# prjct_1.net
KiCad netlist of a schematic drawn in EasyEDA
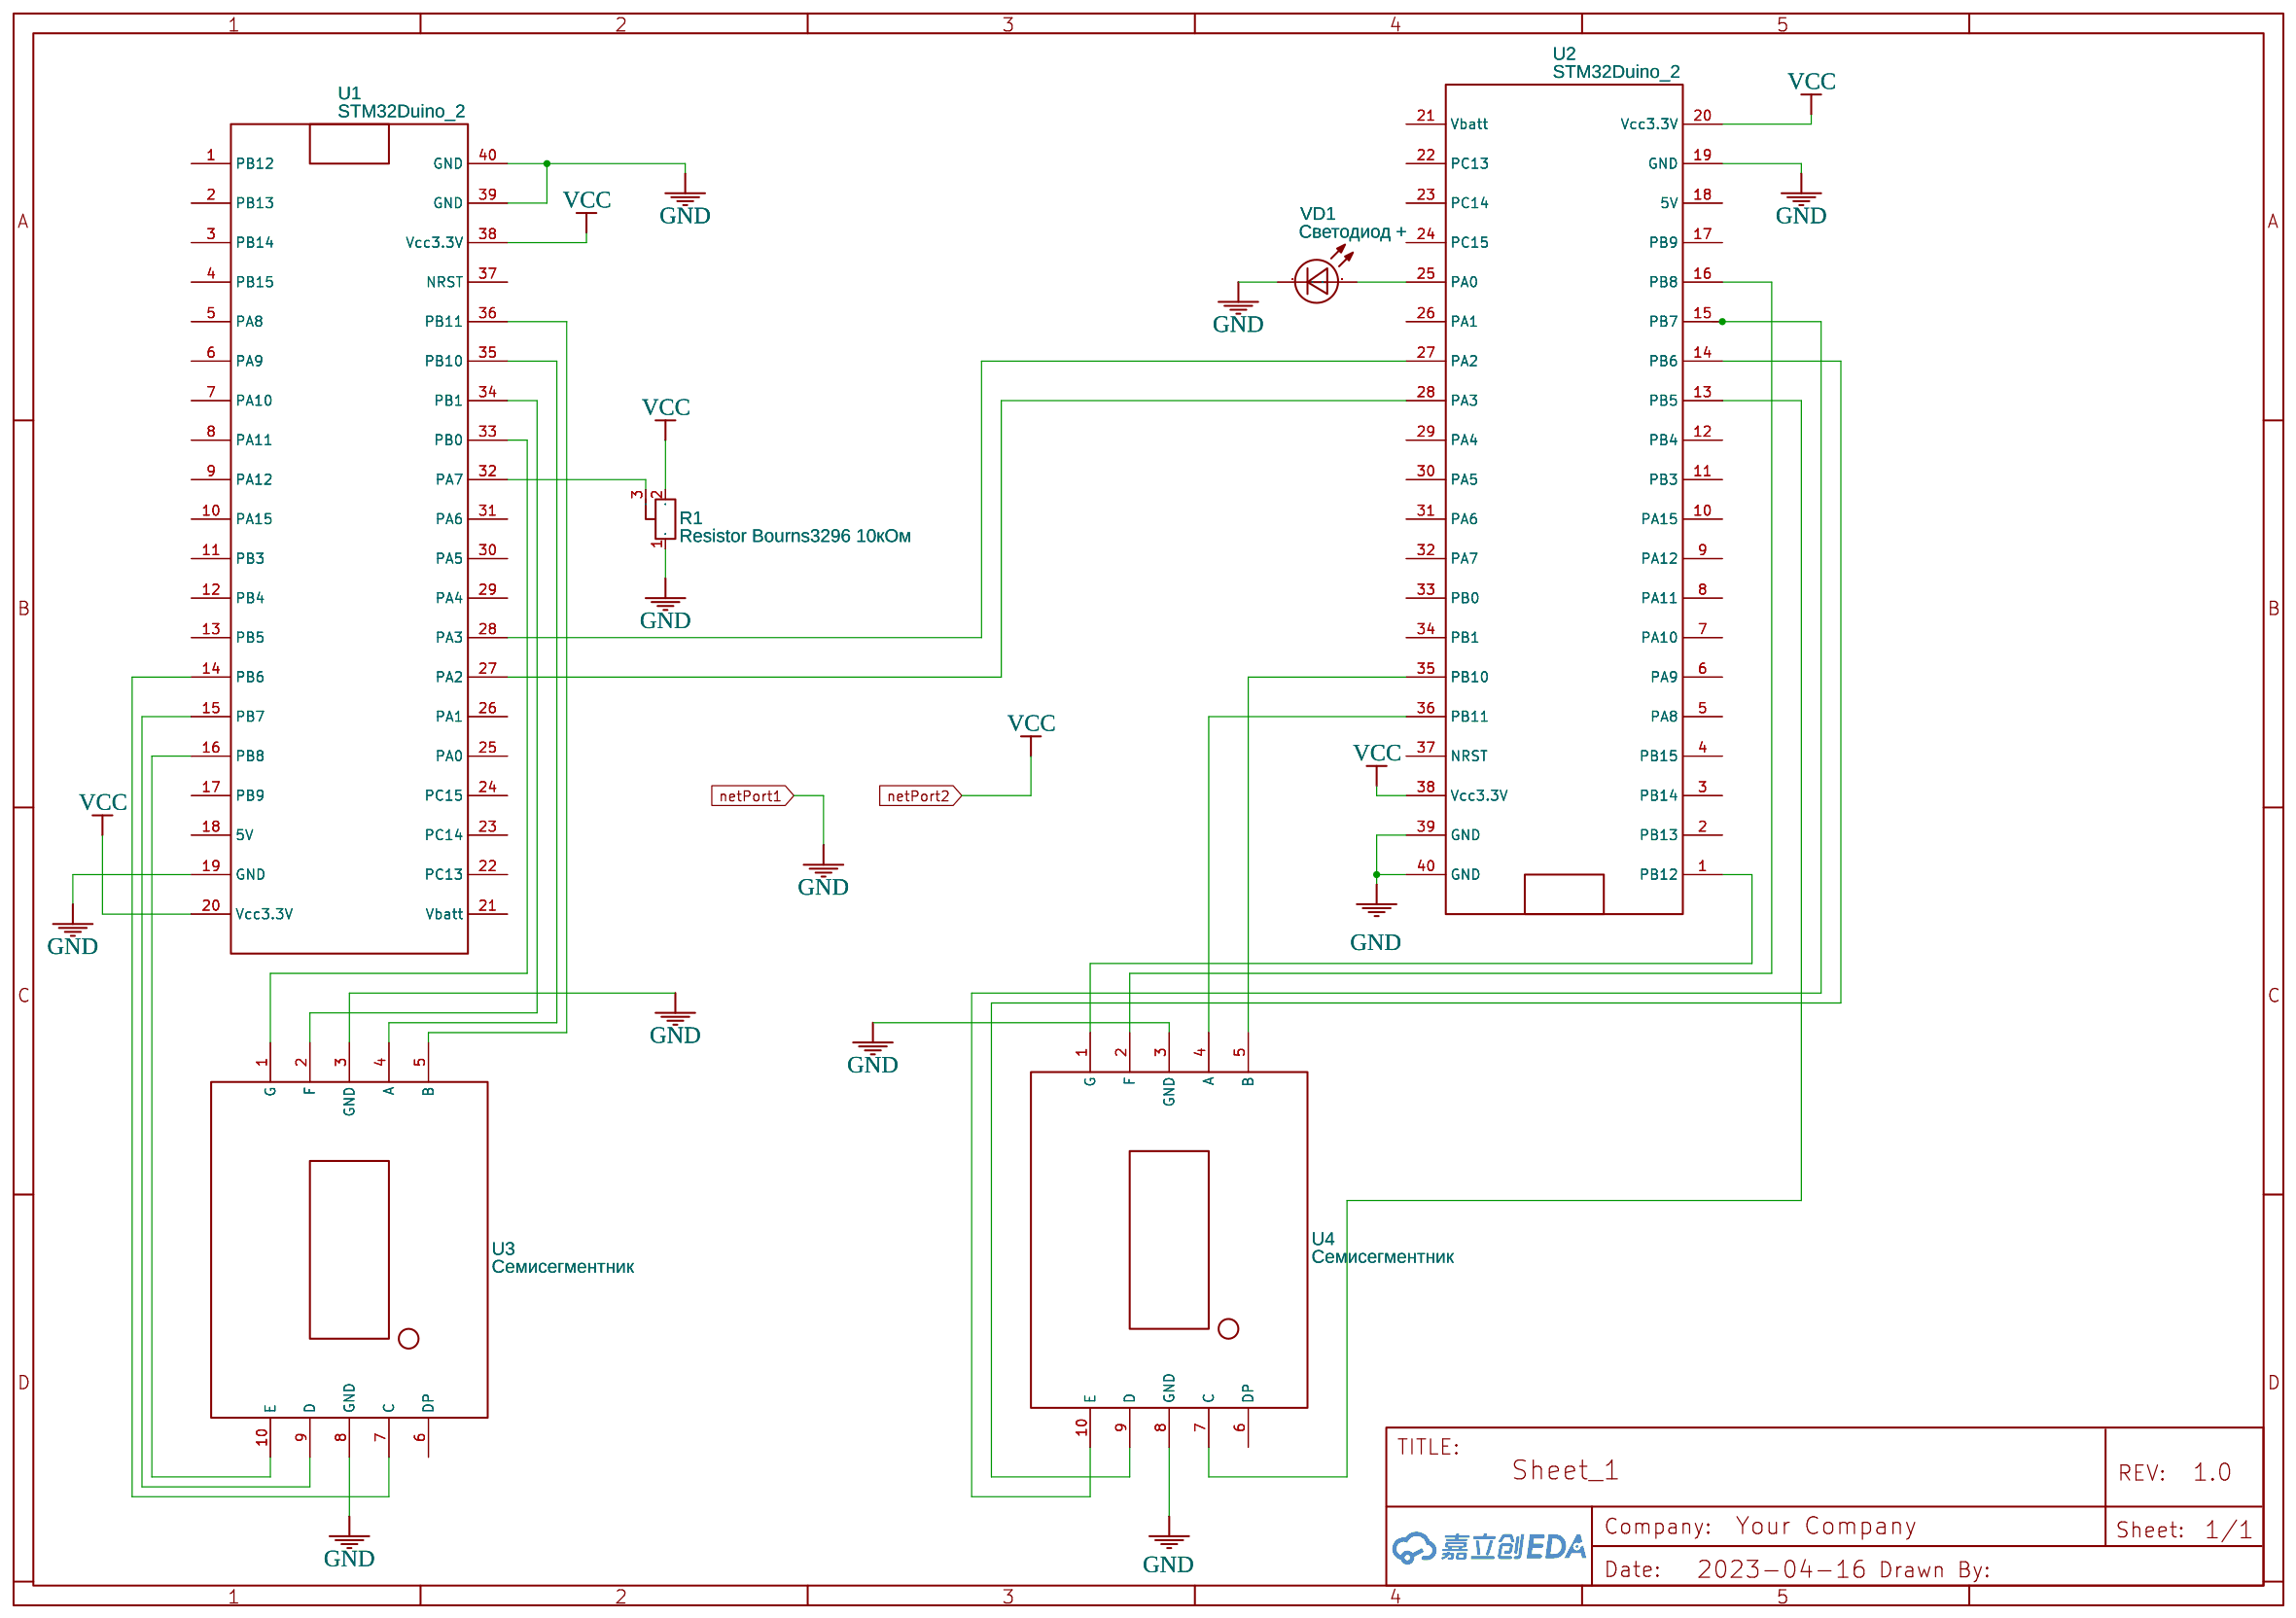
[diagram p0: schematic sheet]

(export (version "E")
  (design (tool "Eeschema 10.0.6"))
  (components
    (comp (ref "R1")
      (value "Resistor Bourns3296 10кОм")
      (libsource (lib "") (part "Resistor Bourns3296 10кОм"))
    )
    (comp (ref "U1")
      (value "STM32Duino_2")
      (fields (field (name "BOM_Manufacturer Part") "STM32Duino"))
      (libsource (lib "") (part "STM32Duino_2_1"))
    )
    (comp (ref "U2")
      (value "STM32Duino_2")
      (fields (field (name "BOM_Manufacturer Part") "STM32Duino"))
      (libsource (lib "") (part "STM32Duino_2"))
    )
    (comp (ref "U3") (value "Семисегментник") (libsource (lib "") (part "Семисегментник")))
    (comp (ref "U4") (value "Семисегментник") (libsource (lib "") (part "Семисегментник")))
    (comp (ref "VD1")
      (value "Светодиод +")
      (fields (field (name "BOM_Manufacturer Part") "Светодиод"))
      (libsource (lib "") (part "Светодиод +"))
    )
  )
  (nets
    (net (code "1") (name "Net-(U1-PA2)") (class "Default")
      (node (ref "U1") (pin "27") (pinfunction "PA2_27") (pintype "unspecified"))
      (node (ref "U2") (pin "28") (pinfunction "PA3_28") (pintype "unspecified"))
    )
    (net (code "2") (name "Net-(U1-PA3)") (class "Default")
      (node (ref "U1") (pin "28") (pinfunction "PA3_28") (pintype "unspecified"))
      (node (ref "U2") (pin "27") (pinfunction "PA2_27") (pintype "unspecified"))
    )
    (net (code "3") (name "Net-(U1-PA7)") (class "Default")
      (node (ref "R1") (pin "3") (pinfunction "3_3") (pintype "unspecified"))
      (node (ref "U1") (pin "32") (pinfunction "PA7_32") (pintype "unspecified"))
    )
    (net (code "4") (name "Net-(U1-PB0)") (class "Default")
      (node (ref "U1") (pin "33") (pinfunction "PB0_33") (pintype "unspecified"))
      (node (ref "U3") (pin "1") (pinfunction "G_1") (pintype "unspecified"))
    )
    (net (code "5") (name "Net-(U1-PB1)") (class "Default")
      (node (ref "U1") (pin "34") (pinfunction "PB1_34") (pintype "unspecified"))
      (node (ref "U3") (pin "2") (pinfunction "F_2") (pintype "unspecified"))
    )
    (net (code "6") (name "Net-(U1-PB6)") (class "Default")
      (node (ref "U1") (pin "14") (pinfunction "PB6_14") (pintype "unspecified"))
      (node (ref "U3") (pin "7") (pinfunction "C_7") (pintype "unspecified"))
    )
    (net (code "7") (name "Net-(U1-PB7)") (class "Default")
      (node (ref "U1") (pin "15") (pinfunction "PB7_15") (pintype "unspecified"))
      (node (ref "U3") (pin "9") (pinfunction "D_9") (pintype "unspecified"))
    )
    (net (code "8") (name "Net-(U1-PB8)") (class "Default")
      (node (ref "U1") (pin "16") (pinfunction "PB8_16") (pintype "unspecified"))
      (node (ref "U3") (pin "10") (pinfunction "E_10") (pintype "unspecified"))
    )
    (net (code "9") (name "Net-(U1-PB10)") (class "Default")
      (node (ref "U1") (pin "35") (pinfunction "PB10_35") (pintype "unspecified"))
      (node (ref "U3") (pin "4") (pinfunction "A_4") (pintype "unspecified"))
    )
    (net (code "10") (name "Net-(U1-PB11)") (class "Default")
      (node (ref "U1") (pin "36") (pinfunction "PB11_36") (pintype "unspecified"))
      (node (ref "U3") (pin "5") (pinfunction "B_5") (pintype "unspecified"))
    )
    (net (code "11") (name "Net-(U2-PA0)") (class "Default")
      (node (ref "U2") (pin "25") (pinfunction "PA0_25") (pintype "unspecified"))
      (node (ref "VD1") (pin "1") (pinfunction "1_1") (pintype "unspecified"))
    )
    (net (code "12") (name "Net-(U2-PB5)") (class "Default")
      (node (ref "U2") (pin "13") (pinfunction "PB5_13") (pintype "unspecified"))
      (node (ref "U4") (pin "7") (pinfunction "C_7") (pintype "unspecified"))
    )
    (net (code "13") (name "Net-(U2-PB6)") (class "Default")
      (node (ref "U2") (pin "14") (pinfunction "PB6_14") (pintype "unspecified"))
      (node (ref "U4") (pin "9") (pinfunction "D_9") (pintype "unspecified"))
    )
    (net (code "14") (name "Net-(U2-PB7)") (class "Default")
      (node (ref "U2") (pin "15") (pinfunction "PB7_15") (pintype "unspecified"))
      (node (ref "U4") (pin "10") (pinfunction "E_10") (pintype "unspecified"))
    )
    (net (code "15") (name "Net-(U2-PB8)") (class "Default")
      (node (ref "U2") (pin "16") (pinfunction "PB8_16") (pintype "unspecified"))
      (node (ref "U4") (pin "2") (pinfunction "F_2") (pintype "unspecified"))
    )
    (net (code "16") (name "Net-(U2-PB10)") (class "Default")
      (node (ref "U2") (pin "35") (pinfunction "PB10_35") (pintype "unspecified"))
      (node (ref "U4") (pin "5") (pinfunction "B_5") (pintype "unspecified"))
    )
    (net (code "17") (name "Net-(U2-PB11)") (class "Default")
      (node (ref "U2") (pin "36") (pinfunction "PB11_36") (pintype "unspecified"))
      (node (ref "U4") (pin "4") (pinfunction "A_4") (pintype "unspecified"))
    )
    (net (code "18") (name "Net-(U2-PB12)") (class "Default")
      (node (ref "U2") (pin "1") (pinfunction "PB12_1") (pintype "unspecified"))
      (node (ref "U4") (pin "1") (pinfunction "G_1") (pintype "unspecified"))
    )
    (net (code "19") (name "netPort1") (class "Default")
      (node (ref "R1") (pin "1") (pinfunction "1_1") (pintype "unspecified"))
      (node (ref "U1") (pin "19") (pinfunction "GND_19") (pintype "unspecified"))
      (node (ref "U1") (pin "39") (pinfunction "GND_39") (pintype "unspecified"))
      (node (ref "U1") (pin "40") (pinfunction "GND_40") (pintype "unspecified"))
      (node (ref "U2") (pin "19") (pinfunction "GND_19") (pintype "unspecified"))
      (node (ref "U2") (pin "39") (pinfunction "GND_39") (pintype "unspecified"))
      (node (ref "U2") (pin "40") (pinfunction "GND_40") (pintype "unspecified"))
      (node (ref "U3") (pin "3") (pinfunction "GND_3") (pintype "unspecified"))
      (node (ref "U3") (pin "8") (pinfunction "GND_8") (pintype "unspecified"))
      (node (ref "U4") (pin "3") (pinfunction "GND_3") (pintype "unspecified"))
      (node (ref "U4") (pin "8") (pinfunction "GND_8") (pintype "unspecified"))
      (node (ref "VD1") (pin "2") (pinfunction "2_2") (pintype "unspecified"))
    )
    (net (code "20") (name "netPort2") (class "Default")
      (node (ref "R1") (pin "2") (pinfunction "2_2") (pintype "unspecified"))
      (node (ref "U1") (pin "20") (pinfunction "Vcc3.3V_20") (pintype "unspecified"))
      (node (ref "U1") (pin "38") (pinfunction "Vcc3.3V_38") (pintype "unspecified"))
      (node (ref "U2") (pin "20") (pinfunction "Vcc3.3V_20") (pintype "unspecified"))
      (node (ref "U2") (pin "38") (pinfunction "Vcc3.3V_38") (pintype "unspecified"))
    )
    (net (code "21") (name "unconnected-(U1-5V-Pad18)") (class "Default")
      (node (ref "U1") (pin "18") (pinfunction "5V_18") (pintype "unspecified"))
    )
    (net (code "22") (name "unconnected-(U1-NRST-Pad37)") (class "Default")
      (node (ref "U1") (pin "37") (pinfunction "NRST_37") (pintype "unspecified"))
    )
    (net (code "23") (name "unconnected-(U1-PA0-Pad25)") (class "Default")
      (node (ref "U1") (pin "25") (pinfunction "PA0_25") (pintype "unspecified"))
    )
    (net (code "24") (name "unconnected-(U1-PA1-Pad26)") (class "Default")
      (node (ref "U1") (pin "26") (pinfunction "PA1_26") (pintype "unspecified"))
    )
    (net (code "25") (name "unconnected-(U1-PA4-Pad29)") (class "Default")
      (node (ref "U1") (pin "29") (pinfunction "PA4_29") (pintype "unspecified"))
    )
    (net (code "26") (name "unconnected-(U1-PA5-Pad30)") (class "Default")
      (node (ref "U1") (pin "30") (pinfunction "PA5_30") (pintype "unspecified"))
    )
    (net (code "27") (name "unconnected-(U1-PA6-Pad31)") (class "Default")
      (node (ref "U1") (pin "31") (pinfunction "PA6_31") (pintype "unspecified"))
    )
    (net (code "28") (name "unconnected-(U1-PA8-Pad5)") (class "Default")
      (node (ref "U1") (pin "5") (pinfunction "PA8_5") (pintype "unspecified"))
    )
    (net (code "29") (name "unconnected-(U1-PA9-Pad6)") (class "Default")
      (node (ref "U1") (pin "6") (pinfunction "PA9_6") (pintype "unspecified"))
    )
    (net (code "30") (name "unconnected-(U1-PA10-Pad7)") (class "Default")
      (node (ref "U1") (pin "7") (pinfunction "PA10_7") (pintype "unspecified"))
    )
    (net (code "31") (name "unconnected-(U1-PA11-Pad8)") (class "Default")
      (node (ref "U1") (pin "8") (pinfunction "PA11_8") (pintype "unspecified"))
    )
    (net (code "32") (name "unconnected-(U1-PA12-Pad9)") (class "Default")
      (node (ref "U1") (pin "9") (pinfunction "PA12_9") (pintype "unspecified"))
    )
    (net (code "33") (name "unconnected-(U1-PA15-Pad10)") (class "Default")
      (node (ref "U1") (pin "10") (pinfunction "PA15_10") (pintype "unspecified"))
    )
    (net (code "34") (name "unconnected-(U1-PB3-Pad11)") (class "Default")
      (node (ref "U1") (pin "11") (pinfunction "PB3_11") (pintype "unspecified"))
    )
    (net (code "35") (name "unconnected-(U1-PB4-Pad12)") (class "Default")
      (node (ref "U1") (pin "12") (pinfunction "PB4_12") (pintype "unspecified"))
    )
    (net (code "36") (name "unconnected-(U1-PB5-Pad13)") (class "Default")
      (node (ref "U1") (pin "13") (pinfunction "PB5_13") (pintype "unspecified"))
    )
    (net (code "37") (name "unconnected-(U1-PB9-Pad17)") (class "Default")
      (node (ref "U1") (pin "17") (pinfunction "PB9_17") (pintype "unspecified"))
    )
    (net (code "38") (name "unconnected-(U1-PB12-Pad1)") (class "Default")
      (node (ref "U1") (pin "1") (pinfunction "PB12_1") (pintype "unspecified"))
    )
    (net (code "39") (name "unconnected-(U1-PB13-Pad2)") (class "Default")
      (node (ref "U1") (pin "2") (pinfunction "PB13_2") (pintype "unspecified"))
    )
    (net (code "40") (name "unconnected-(U1-PB14-Pad3)") (class "Default")
      (node (ref "U1") (pin "3") (pinfunction "PB14_3") (pintype "unspecified"))
    )
    (net (code "41") (name "unconnected-(U1-PB15-Pad4)") (class "Default")
      (node (ref "U1") (pin "4") (pinfunction "PB15_4") (pintype "unspecified"))
    )
    (net (code "42") (name "unconnected-(U1-PC13-Pad22)") (class "Default")
      (node (ref "U1") (pin "22") (pinfunction "PC13_22") (pintype "unspecified"))
    )
    (net (code "43") (name "unconnected-(U1-PC14-Pad23)") (class "Default")
      (node (ref "U1") (pin "23") (pinfunction "PC14_23") (pintype "unspecified"))
    )
    (net (code "44") (name "unconnected-(U1-PC15-Pad24)") (class "Default")
      (node (ref "U1") (pin "24") (pinfunction "PC15_24") (pintype "unspecified"))
    )
    (net (code "45") (name "unconnected-(U1-Vbatt-Pad21)") (class "Default")
      (node (ref "U1") (pin "21") (pinfunction "Vbatt_21") (pintype "unspecified"))
    )
    (net (code "46") (name "unconnected-(U2-5V-Pad18)") (class "Default")
      (node (ref "U2") (pin "18") (pinfunction "5V_18") (pintype "unspecified"))
    )
    (net (code "47") (name "unconnected-(U2-NRST-Pad37)") (class "Default")
      (node (ref "U2") (pin "37") (pinfunction "NRST_37") (pintype "unspecified"))
    )
    (net (code "48") (name "unconnected-(U2-PA1-Pad26)") (class "Default")
      (node (ref "U2") (pin "26") (pinfunction "PA1_26") (pintype "unspecified"))
    )
    (net (code "49") (name "unconnected-(U2-PA4-Pad29)") (class "Default")
      (node (ref "U2") (pin "29") (pinfunction "PA4_29") (pintype "unspecified"))
    )
    (net (code "50") (name "unconnected-(U2-PA5-Pad30)") (class "Default")
      (node (ref "U2") (pin "30") (pinfunction "PA5_30") (pintype "unspecified"))
    )
    (net (code "51") (name "unconnected-(U2-PA6-Pad31)") (class "Default")
      (node (ref "U2") (pin "31") (pinfunction "PA6_31") (pintype "unspecified"))
    )
    (net (code "52") (name "unconnected-(U2-PA7-Pad32)") (class "Default")
      (node (ref "U2") (pin "32") (pinfunction "PA7_32") (pintype "unspecified"))
    )
    (net (code "53") (name "unconnected-(U2-PA8-Pad5)") (class "Default")
      (node (ref "U2") (pin "5") (pinfunction "PA8_5") (pintype "unspecified"))
    )
    (net (code "54") (name "unconnected-(U2-PA9-Pad6)") (class "Default")
      (node (ref "U2") (pin "6") (pinfunction "PA9_6") (pintype "unspecified"))
    )
    (net (code "55") (name "unconnected-(U2-PA10-Pad7)") (class "Default")
      (node (ref "U2") (pin "7") (pinfunction "PA10_7") (pintype "unspecified"))
    )
    (net (code "56") (name "unconnected-(U2-PA11-Pad8)") (class "Default")
      (node (ref "U2") (pin "8") (pinfunction "PA11_8") (pintype "unspecified"))
    )
    (net (code "57") (name "unconnected-(U2-PA12-Pad9)") (class "Default")
      (node (ref "U2") (pin "9") (pinfunction "PA12_9") (pintype "unspecified"))
    )
    (net (code "58") (name "unconnected-(U2-PA15-Pad10)") (class "Default")
      (node (ref "U2") (pin "10") (pinfunction "PA15_10") (pintype "unspecified"))
    )
    (net (code "59") (name "unconnected-(U2-PB0-Pad33)") (class "Default")
      (node (ref "U2") (pin "33") (pinfunction "PB0_33") (pintype "unspecified"))
    )
    (net (code "60") (name "unconnected-(U2-PB1-Pad34)") (class "Default")
      (node (ref "U2") (pin "34") (pinfunction "PB1_34") (pintype "unspecified"))
    )
    (net (code "61") (name "unconnected-(U2-PB3-Pad11)") (class "Default")
      (node (ref "U2") (pin "11") (pinfunction "PB3_11") (pintype "unspecified"))
    )
    (net (code "62") (name "unconnected-(U2-PB4-Pad12)") (class "Default")
      (node (ref "U2") (pin "12") (pinfunction "PB4_12") (pintype "unspecified"))
    )
    (net (code "63") (name "unconnected-(U2-PB9-Pad17)") (class "Default")
      (node (ref "U2") (pin "17") (pinfunction "PB9_17") (pintype "unspecified"))
    )
    (net (code "64") (name "unconnected-(U2-PB13-Pad2)") (class "Default")
      (node (ref "U2") (pin "2") (pinfunction "PB13_2") (pintype "unspecified"))
    )
    (net (code "65") (name "unconnected-(U2-PB14-Pad3)") (class "Default")
      (node (ref "U2") (pin "3") (pinfunction "PB14_3") (pintype "unspecified"))
    )
    (net (code "66") (name "unconnected-(U2-PB15-Pad4)") (class "Default")
      (node (ref "U2") (pin "4") (pinfunction "PB15_4") (pintype "unspecified"))
    )
    (net (code "67") (name "unconnected-(U2-PC13-Pad22)") (class "Default")
      (node (ref "U2") (pin "22") (pinfunction "PC13_22") (pintype "unspecified"))
    )
    (net (code "68") (name "unconnected-(U2-PC14-Pad23)") (class "Default")
      (node (ref "U2") (pin "23") (pinfunction "PC14_23") (pintype "unspecified"))
    )
    (net (code "69") (name "unconnected-(U2-PC15-Pad24)") (class "Default")
      (node (ref "U2") (pin "24") (pinfunction "PC15_24") (pintype "unspecified"))
    )
    (net (code "70") (name "unconnected-(U2-Vbatt-Pad21)") (class "Default")
      (node (ref "U2") (pin "21") (pinfunction "Vbatt_21") (pintype "unspecified"))
    )
    (net (code "71") (name "unconnected-(U3-DP-Pad6)") (class "Default")
      (node (ref "U3") (pin "6") (pinfunction "DP_6") (pintype "unspecified"))
    )
    (net (code "72") (name "unconnected-(U4-DP-Pad6)") (class "Default")
      (node (ref "U4") (pin "6") (pinfunction "DP_6") (pintype "unspecified"))
    )
  )
)
